# Led_Board.net
KiCad netlist of a schematic drawn in EAGLE
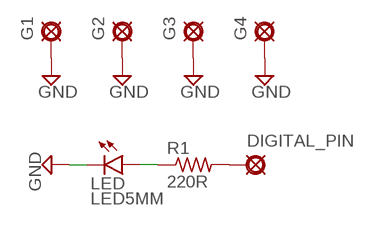
[diagram p0: schematic, sheet 1]

(export (version "E")
  (design (tool "Eeschema 10.0.6"))
  (components
    (comp (ref "DIGITAL_PIN")
      (value "PADO")
      (footprint "eagle-import:ROUND")
      (libsource (lib "eagle-import") (part "PADO"))
    )
    (comp (ref "G1")
      (value "PADO")
      (footprint "eagle-import:ROUND")
      (libsource (lib "eagle-import") (part "PADO"))
    )
    (comp (ref "G2")
      (value "PADO")
      (footprint "eagle-import:ROUND")
      (libsource (lib "eagle-import") (part "PADO"))
    )
    (comp (ref "G3")
      (value "PADO")
      (footprint "eagle-import:ROUND")
      (libsource (lib "eagle-import") (part "PADO"))
    )
    (comp (ref "G4")
      (value "PADO")
      (footprint "eagle-import:ROUND")
      (libsource (lib "eagle-import") (part "PADO"))
    )
    (comp (ref "LED")
      (value "LED5MM")
      (footprint "eagle-import:LED5MM")
      (libsource (lib "eagle-import") (part "LED5MM"))
    )
    (comp (ref "R1")
      (value "220R")
      (footprint "eagle-import:R0207_3")
      (libsource (lib "eagle-import") (part "6MM.3"))
    )
  )
  (nets
    (net (code "1") (name "GND") (class "Default")
      (node (ref "G1") (pin "1") (pinfunction "PAD_1") (pintype "passive"))
      (node (ref "G2") (pin "1") (pinfunction "PAD_1") (pintype "passive"))
      (node (ref "G3") (pin "1") (pinfunction "PAD_1") (pintype "passive"))
      (node (ref "G4") (pin "1") (pinfunction "PAD_1") (pintype "passive"))
      (node (ref "LED") (pin "K") (pinfunction "C_K") (pintype "passive"))
    )
    (net (code "2") (name "Net-(DIGITAL_PIN-PAD)") (class "Default")
      (node (ref "DIGITAL_PIN") (pin "1") (pinfunction "PAD_1") (pintype "passive"))
      (node (ref "R1") (pin "2") (pinfunction "2_2") (pintype "passive"))
    )
    (net (code "3") (name "Net-(LED-PadA)") (class "Default")
      (node (ref "LED") (pin "A") (pinfunction "A_A") (pintype "passive"))
      (node (ref "R1") (pin "1") (pinfunction "1_1") (pintype "passive"))
    )
  )
)
